# adapter-50-100mil-x8.net
KiCad netlist of a schematic drawn in Altium Designer
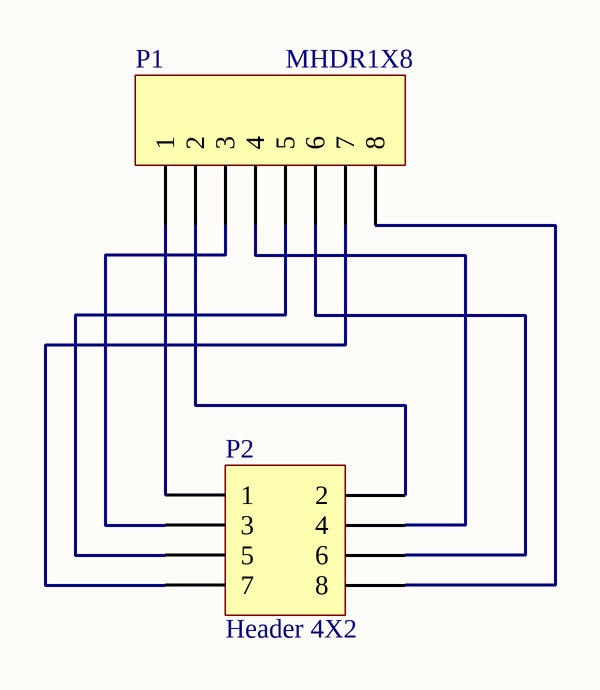
[diagram p0: adapter-50-100mil-x8.SchDoc]

(export (version "E")
  (design (tool "Eeschema 10.0.6"))
  (components
    (comp (ref "P1")
      (value "MHDR1X8")
      (footprint "MHDR1X8")
      (description "Header, 8-Pin")
      (fields (field (name "PUBLISHER") "Altium Limited"))
      (libsource (lib "Miscellaneous Connectors") (part "MHDR1X8"))
    )
    (comp (ref "P2")
      (value "Header 4X2")
      (footprint "HDR2X4")
      (description "Header, 4-Pin, Dual row")
      (fields (field (name "PUBLISHER") "Altium Limited"))
      (libsource (lib "Miscellaneous Connectors") (part "Header 4X2"))
    )
  )
  (nets
    (net (code "1") (name "Net-(P1-Pad1)") (class "Default")
      (node (ref "P1") (pin "1") (pinfunction "1_1") (pintype "passive"))
      (node (ref "P2") (pin "1") (pinfunction "1_1") (pintype "passive"))
    )
    (net (code "2") (name "Net-(P1-Pad2)") (class "Default")
      (node (ref "P1") (pin "2") (pinfunction "2_2") (pintype "passive"))
      (node (ref "P2") (pin "2") (pinfunction "2_2") (pintype "passive"))
    )
    (net (code "3") (name "Net-(P1-Pad3)") (class "Default")
      (node (ref "P1") (pin "3") (pinfunction "3_3") (pintype "passive"))
      (node (ref "P2") (pin "3") (pinfunction "3_3") (pintype "passive"))
    )
    (net (code "4") (name "Net-(P1-Pad4)") (class "Default")
      (node (ref "P1") (pin "4") (pinfunction "4_4") (pintype "passive"))
      (node (ref "P2") (pin "4") (pinfunction "4_4") (pintype "passive"))
    )
    (net (code "5") (name "Net-(P1-Pad5)") (class "Default")
      (node (ref "P1") (pin "5") (pinfunction "5_5") (pintype "passive"))
      (node (ref "P2") (pin "5") (pinfunction "5_5") (pintype "passive"))
    )
    (net (code "6") (name "Net-(P1-Pad6)") (class "Default")
      (node (ref "P1") (pin "6") (pinfunction "6_6") (pintype "passive"))
      (node (ref "P2") (pin "6") (pinfunction "6_6") (pintype "passive"))
    )
    (net (code "7") (name "Net-(P1-Pad7)") (class "Default")
      (node (ref "P1") (pin "7") (pinfunction "7_7") (pintype "passive"))
      (node (ref "P2") (pin "7") (pinfunction "7_7") (pintype "passive"))
    )
    (net (code "8") (name "Net-(P1-Pad8)") (class "Default")
      (node (ref "P1") (pin "8") (pinfunction "8_8") (pintype "passive"))
      (node (ref "P2") (pin "8") (pinfunction "8_8") (pintype "passive"))
    )
  )
)
